# panel.net
KiCad netlist of a schematic drawn in EAGLE
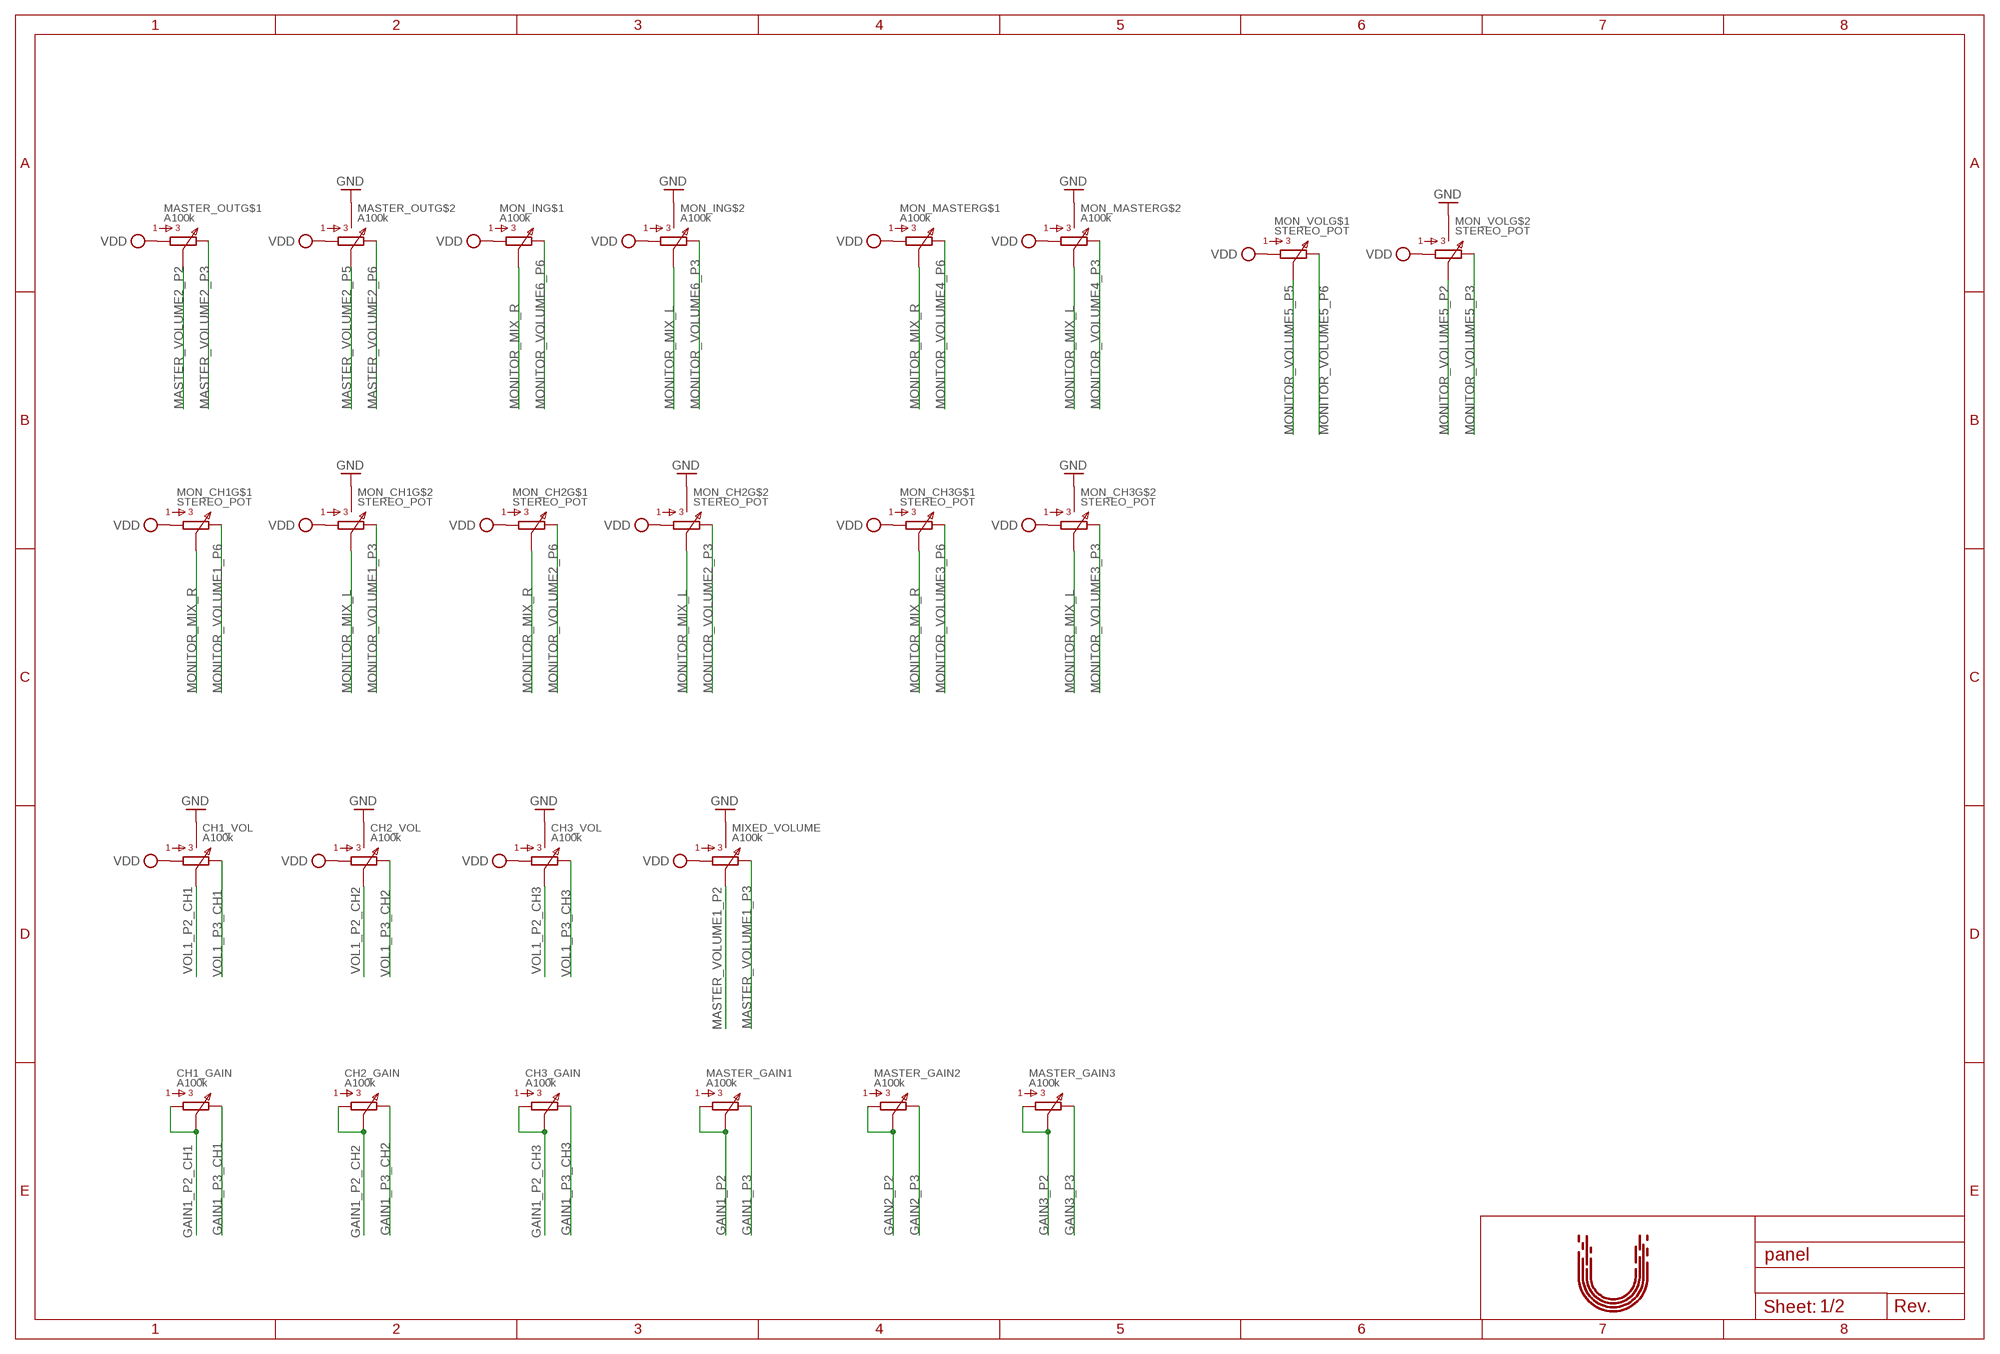
[diagram p0: schematic, sheet 1]
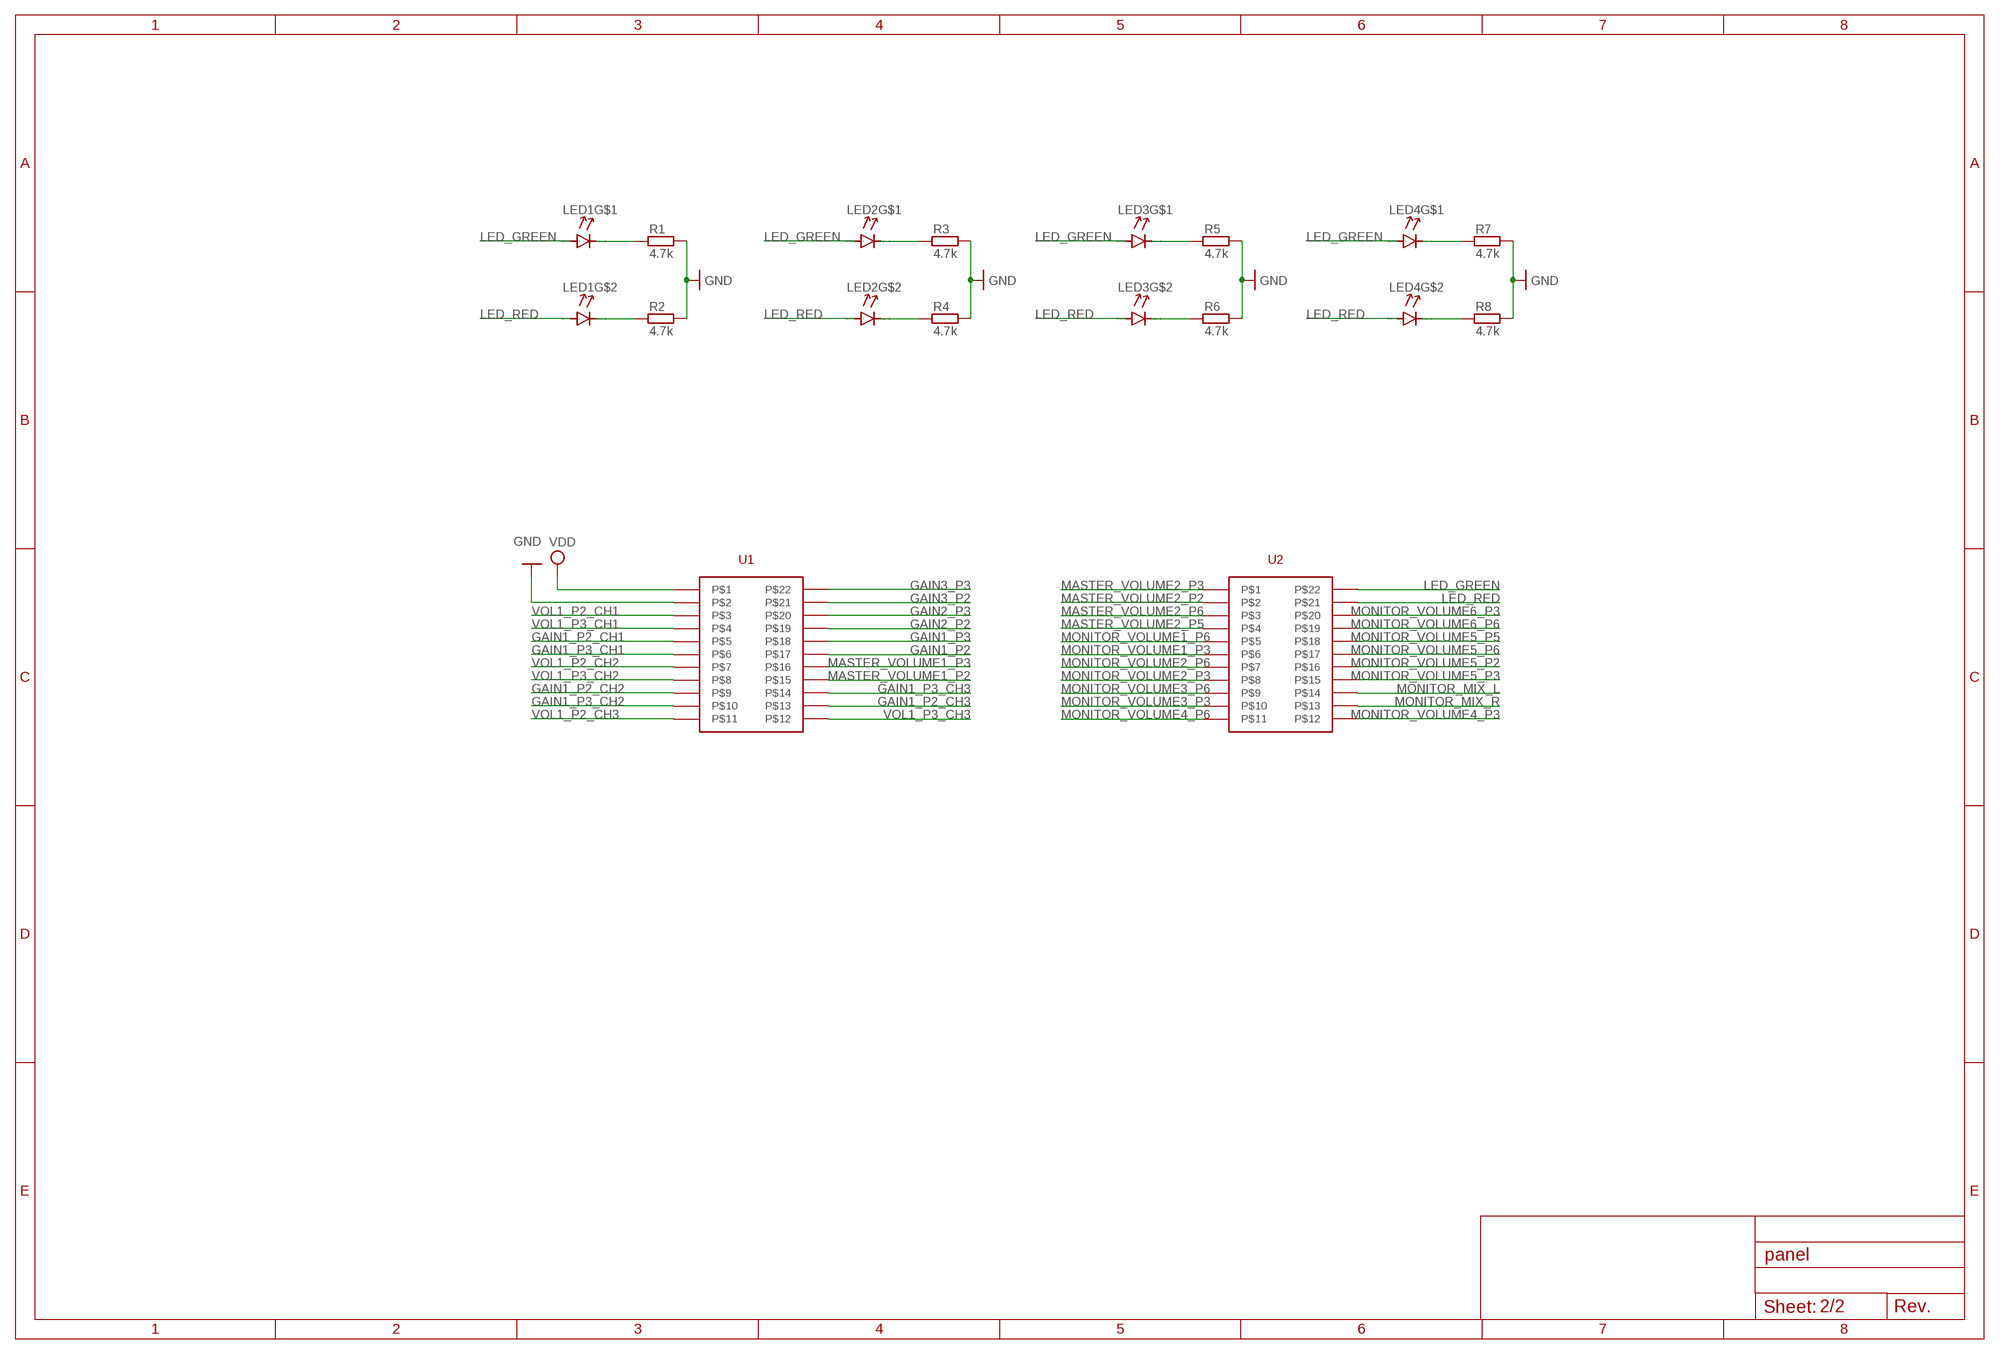
[diagram p1: schematic, sheet 2]

(export (version "E")
  (design (tool "Eeschema 10.0.6"))
  (components
    (comp (ref "CH1_GAIN")
      (value "A100k")
      (footprint "eagle-import:3296W")
      (fields (field (name "MPN") "3296W-1-104RLF"))
      (libsource (lib "eagle-import") (part "TRIMPOT"))
    )
    (comp (ref "CH1_VOL")
      (value "A100k")
      (footprint "eagle-import:P0915N")
      (fields (field (name "MPN") "P0915N-QC15AR100K"))
      (libsource (lib "eagle-import") (part "POT"))
    )
    (comp (ref "CH2_GAIN")
      (value "A100k")
      (footprint "eagle-import:3296W")
      (fields (field (name "MPN") "3296W-1-104RLF"))
      (libsource (lib "eagle-import") (part "TRIMPOT"))
    )
    (comp (ref "CH2_VOL")
      (value "A100k")
      (footprint "eagle-import:P0915N")
      (fields (field (name "MPN") "P0915N-QC15AR100K"))
      (libsource (lib "eagle-import") (part "POT"))
    )
    (comp (ref "CH3_GAIN")
      (value "A100k")
      (footprint "eagle-import:3296W")
      (fields (field (name "MPN") "3296W-1-104RLF"))
      (libsource (lib "eagle-import") (part "TRIMPOT"))
    )
    (comp (ref "CH3_VOL")
      (value "A100k")
      (footprint "eagle-import:P0915N")
      (fields (field (name "MPN") "P0915N-QC15AR100K"))
      (libsource (lib "eagle-import") (part "POT"))
    )
    (comp (ref "MASTER_GAIN1")
      (value "A100k")
      (footprint "eagle-import:3296W")
      (fields (field (name "MPN") "3296W-1-104RLF"))
      (libsource (lib "eagle-import") (part "TRIMPOT"))
    )
    (comp (ref "MASTER_GAIN2")
      (value "A100k")
      (footprint "eagle-import:3296W")
      (fields (field (name "MPN") "3296W-1-104RLF"))
      (libsource (lib "eagle-import") (part "TRIMPOT"))
    )
    (comp (ref "MASTER_GAIN3")
      (value "A100k")
      (footprint "eagle-import:3296W")
      (fields (field (name "MPN") "3296W-1-104RLF"))
      (libsource (lib "eagle-import") (part "TRIMPOT"))
    )
    (comp (ref "MASTER_OUT")
      (value "A100k")
      (footprint "eagle-import:P0925N")
      (fields (field (name "MPN") "P0925N-FC20AR100K"))
      (libsource (lib "eagle-import") (part "STEREO_POT"))
    )
    (comp (ref "MIXED_VOLUME")
      (value "A100k")
      (footprint "eagle-import:P0915N")
      (fields (field (name "MPN") "P0915N-QC15AR100K"))
      (libsource (lib "eagle-import") (part "POT"))
    )
    (comp (ref "MON_CH1")
      (value "STEREO_POT")
      (footprint "eagle-import:P0925N")
      (fields (field (name "MPN") "P0925N-FC20AR100K"))
      (libsource (lib "eagle-import") (part "STEREO_POT"))
    )
    (comp (ref "MON_CH2")
      (value "STEREO_POT")
      (footprint "eagle-import:P0925N")
      (fields (field (name "MPN") "P0925N-FC20AR100K"))
      (libsource (lib "eagle-import") (part "STEREO_POT"))
    )
    (comp (ref "MON_CH3")
      (value "STEREO_POT")
      (footprint "eagle-import:P0925N")
      (fields (field (name "MPN") "P0925N-FC20AR100K"))
      (libsource (lib "eagle-import") (part "STEREO_POT"))
    )
    (comp (ref "MON_IN")
      (value "A100k")
      (footprint "eagle-import:P0925N")
      (fields (field (name "MPN") "P0925N-FC20AR100K"))
      (libsource (lib "eagle-import") (part "STEREO_POT"))
    )
    (comp (ref "MON_MASTER")
      (value "A100k")
      (footprint "eagle-import:P0925N")
      (fields (field (name "MPN") "P0925N-FC20AR100K"))
      (libsource (lib "eagle-import") (part "STEREO_POT"))
    )
    (comp (ref "MON_VOL")
      (value "STEREO_POT")
      (footprint "eagle-import:P0925N")
      (fields (field (name "MPN") "P0925N-FC20AR100K"))
      (libsource (lib "eagle-import") (part "STEREO_POT"))
    )
    (comp (ref "U$1")
      (value "UTBULT_DESIGN4")
      (footprint "eagle-import:UD_4")
      (libsource (lib "eagle-import") (part "UTBULT_DESIGN4"))
    )
    (comp (ref "LED1")
      (value "DUAL_LEDDUAL_LED")
      (footprint "eagle-import:RESCAXE40P80X160X50-4N")
      (fields (field (name "MPN") "HSMF-C162"))
      (libsource (lib "eagle-import") (part "DUAL_LEDDUAL_LED"))
    )
    (comp (ref "LED2")
      (value "DUAL_LEDDUAL_LED")
      (footprint "eagle-import:RESCAXE40P80X160X50-4N")
      (fields (field (name "MPN") "HSMF-C162"))
      (libsource (lib "eagle-import") (part "DUAL_LEDDUAL_LED"))
    )
    (comp (ref "LED3")
      (value "DUAL_LEDDUAL_LED")
      (footprint "eagle-import:RESCAXE40P80X160X50-4N")
      (fields (field (name "MPN") "HSMF-C162"))
      (libsource (lib "eagle-import") (part "DUAL_LEDDUAL_LED"))
    )
    (comp (ref "LED4")
      (value "DUAL_LEDDUAL_LED")
      (footprint "eagle-import:RESCAXE40P80X160X50-4N")
      (fields (field (name "MPN") "HSMF-C162"))
      (libsource (lib "eagle-import") (part "DUAL_LEDDUAL_LED"))
    )
    (comp (ref "R1")
      (value "4.7k")
      (footprint "eagle-import:R0603")
      (libsource (lib "eagle-import") (part "RESISTOR"))
    )
    (comp (ref "R2")
      (value "4.7k")
      (footprint "eagle-import:R0603")
      (libsource (lib "eagle-import") (part "RESISTOR"))
    )
    (comp (ref "R3")
      (value "4.7k")
      (footprint "eagle-import:R0603")
      (libsource (lib "eagle-import") (part "RESISTOR"))
    )
    (comp (ref "R4")
      (value "4.7k")
      (footprint "eagle-import:R0603")
      (libsource (lib "eagle-import") (part "RESISTOR"))
    )
    (comp (ref "R5")
      (value "4.7k")
      (footprint "eagle-import:R0603")
      (libsource (lib "eagle-import") (part "RESISTOR"))
    )
    (comp (ref "R6")
      (value "4.7k")
      (footprint "eagle-import:R0603")
      (libsource (lib "eagle-import") (part "RESISTOR"))
    )
    (comp (ref "R7")
      (value "4.7k")
      (footprint "eagle-import:R0603")
      (libsource (lib "eagle-import") (part "RESISTOR"))
    )
    (comp (ref "R8")
      (value "4.7k")
      (footprint "eagle-import:R0603")
      (libsource (lib "eagle-import") (part "RESISTOR"))
    )
    (comp (ref "U1")
      (value "22PINHEADER22PINHEADER")
      (footprint "eagle-import:HDRV22W64P254_2X11_2794X508X838B")
      (libsource (lib "eagle-import") (part "22PINHEADER22PINHEADER"))
    )
    (comp (ref "U2")
      (value "22PINHEADER22PINHEADER")
      (footprint "eagle-import:HDRV22W64P254_2X11_2794X508X838B")
      (libsource (lib "eagle-import") (part "22PINHEADER22PINHEADER"))
    )
  )
  (nets
    (net (code "1") (name "GAIN1_P2") (class "Default")
      (node (ref "MASTER_GAIN1") (pin "P$1") (pinfunction "1_P$1") (pintype "passive"))
      (node (ref "MASTER_GAIN1") (pin "P$2") (pinfunction "2_P$2") (pintype "passive"))
      (node (ref "U1") (pin "17") (pinfunction "P$17_17") (pintype "bidirectional"))
    )
    (net (code "2") (name "GAIN1_P2_CH1") (class "Default")
      (node (ref "CH1_GAIN") (pin "P$1") (pinfunction "1_P$1") (pintype "passive"))
      (node (ref "CH1_GAIN") (pin "P$2") (pinfunction "2_P$2") (pintype "passive"))
      (node (ref "U1") (pin "5") (pinfunction "P$5_5") (pintype "bidirectional"))
    )
    (net (code "3") (name "GAIN1_P2_CH2") (class "Default")
      (node (ref "CH2_GAIN") (pin "P$1") (pinfunction "1_P$1") (pintype "passive"))
      (node (ref "CH2_GAIN") (pin "P$2") (pinfunction "2_P$2") (pintype "passive"))
      (node (ref "U1") (pin "9") (pinfunction "P$9_9") (pintype "bidirectional"))
    )
    (net (code "4") (name "GAIN1_P2_CH3") (class "Default")
      (node (ref "CH3_GAIN") (pin "P$1") (pinfunction "1_P$1") (pintype "passive"))
      (node (ref "CH3_GAIN") (pin "P$2") (pinfunction "2_P$2") (pintype "passive"))
      (node (ref "U1") (pin "13") (pinfunction "P$13_13") (pintype "bidirectional"))
    )
    (net (code "5") (name "GAIN1_P3") (class "Default")
      (node (ref "MASTER_GAIN1") (pin "P$3") (pinfunction "3_P$3") (pintype "passive"))
      (node (ref "U1") (pin "18") (pinfunction "P$18_18") (pintype "bidirectional"))
    )
    (net (code "6") (name "GAIN1_P3_CH1") (class "Default")
      (node (ref "CH1_GAIN") (pin "P$3") (pinfunction "3_P$3") (pintype "passive"))
      (node (ref "U1") (pin "6") (pinfunction "P$6_6") (pintype "bidirectional"))
    )
    (net (code "7") (name "GAIN1_P3_CH2") (class "Default")
      (node (ref "CH2_GAIN") (pin "P$3") (pinfunction "3_P$3") (pintype "passive"))
      (node (ref "U1") (pin "10") (pinfunction "P$10_10") (pintype "bidirectional"))
    )
    (net (code "8") (name "GAIN1_P3_CH3") (class "Default")
      (node (ref "CH3_GAIN") (pin "P$3") (pinfunction "3_P$3") (pintype "passive"))
      (node (ref "U1") (pin "14") (pinfunction "P$14_14") (pintype "bidirectional"))
    )
    (net (code "9") (name "GAIN2_P2") (class "Default")
      (node (ref "MASTER_GAIN2") (pin "P$1") (pinfunction "1_P$1") (pintype "passive"))
      (node (ref "MASTER_GAIN2") (pin "P$2") (pinfunction "2_P$2") (pintype "passive"))
      (node (ref "U1") (pin "19") (pinfunction "P$19_19") (pintype "bidirectional"))
    )
    (net (code "10") (name "GAIN2_P3") (class "Default")
      (node (ref "MASTER_GAIN2") (pin "P$3") (pinfunction "3_P$3") (pintype "passive"))
      (node (ref "U1") (pin "20") (pinfunction "P$20_20") (pintype "bidirectional"))
    )
    (net (code "11") (name "GAIN3_P2") (class "Default")
      (node (ref "MASTER_GAIN3") (pin "P$1") (pinfunction "1_P$1") (pintype "passive"))
      (node (ref "MASTER_GAIN3") (pin "P$2") (pinfunction "2_P$2") (pintype "passive"))
      (node (ref "U1") (pin "21") (pinfunction "P$21_21") (pintype "bidirectional"))
    )
    (net (code "12") (name "GAIN3_P3") (class "Default")
      (node (ref "MASTER_GAIN3") (pin "P$3") (pinfunction "3_P$3") (pintype "passive"))
      (node (ref "U1") (pin "22") (pinfunction "P$22_22") (pintype "bidirectional"))
    )
    (net (code "13") (name "GND") (class "Default")
      (node (ref "CH1_VOL") (pin "P$7") (pinfunction "P$1_P$7") (pintype "bidirectional"))
      (node (ref "CH1_VOL") (pin "P$8") (pinfunction "P$1_P$8") (pintype "bidirectional"))
      (node (ref "CH2_VOL") (pin "P$7") (pinfunction "P$1_P$7") (pintype "bidirectional"))
      (node (ref "CH2_VOL") (pin "P$8") (pinfunction "P$1_P$8") (pintype "bidirectional"))
      (node (ref "CH3_VOL") (pin "P$7") (pinfunction "P$1_P$7") (pintype "bidirectional"))
      (node (ref "CH3_VOL") (pin "P$8") (pinfunction "P$1_P$8") (pintype "bidirectional"))
      (node (ref "MASTER_OUT") (pin "P$7") (pinfunction "P$1_P$7") (pintype "bidirectional"))
      (node (ref "MASTER_OUT") (pin "P$8") (pinfunction "P$1_P$8") (pintype "bidirectional"))
      (node (ref "MIXED_VOLUME") (pin "P$7") (pinfunction "P$1_P$7") (pintype "bidirectional"))
      (node (ref "MIXED_VOLUME") (pin "P$8") (pinfunction "P$1_P$8") (pintype "bidirectional"))
      (node (ref "MON_CH1") (pin "P$7") (pinfunction "P$1_P$7") (pintype "bidirectional"))
      (node (ref "MON_CH1") (pin "P$8") (pinfunction "P$1_P$8") (pintype "bidirectional"))
      (node (ref "MON_CH2") (pin "P$7") (pinfunction "P$1_P$7") (pintype "bidirectional"))
      (node (ref "MON_CH2") (pin "P$8") (pinfunction "P$1_P$8") (pintype "bidirectional"))
      (node (ref "MON_CH3") (pin "P$7") (pinfunction "P$1_P$7") (pintype "bidirectional"))
      (node (ref "MON_CH3") (pin "P$8") (pinfunction "P$1_P$8") (pintype "bidirectional"))
      (node (ref "MON_IN") (pin "P$7") (pinfunction "P$1_P$7") (pintype "bidirectional"))
      (node (ref "MON_IN") (pin "P$8") (pinfunction "P$1_P$8") (pintype "bidirectional"))
      (node (ref "MON_MASTER") (pin "P$7") (pinfunction "P$1_P$7") (pintype "bidirectional"))
      (node (ref "MON_MASTER") (pin "P$8") (pinfunction "P$1_P$8") (pintype "bidirectional"))
      (node (ref "MON_VOL") (pin "P$7") (pinfunction "P$1_P$7") (pintype "bidirectional"))
      (node (ref "MON_VOL") (pin "P$8") (pinfunction "P$1_P$8") (pintype "bidirectional"))
      (node (ref "R1") (pin "2") (pinfunction "2_2") (pintype "passive"))
      (node (ref "R2") (pin "2") (pinfunction "2_2") (pintype "passive"))
      (node (ref "R3") (pin "2") (pinfunction "2_2") (pintype "passive"))
      (node (ref "R4") (pin "2") (pinfunction "2_2") (pintype "passive"))
      (node (ref "R5") (pin "2") (pinfunction "2_2") (pintype "passive"))
      (node (ref "R6") (pin "2") (pinfunction "2_2") (pintype "passive"))
      (node (ref "R7") (pin "2") (pinfunction "2_2") (pintype "passive"))
      (node (ref "R8") (pin "2") (pinfunction "2_2") (pintype "passive"))
      (node (ref "U1") (pin "2") (pinfunction "P$2_2") (pintype "bidirectional"))
    )
    (net (code "14") (name "LED_GREEN") (class "Default")
      (node (ref "LED1") (pin "1") (pinfunction "A_1") (pintype "passive"))
      (node (ref "LED2") (pin "1") (pinfunction "A_1") (pintype "passive"))
      (node (ref "LED3") (pin "1") (pinfunction "A_1") (pintype "passive"))
      (node (ref "LED4") (pin "1") (pinfunction "A_1") (pintype "passive"))
      (node (ref "U2") (pin "22") (pinfunction "P$22_22") (pintype "bidirectional"))
    )
    (net (code "15") (name "LED_RED") (class "Default")
      (node (ref "LED1") (pin "2") (pinfunction "A_2") (pintype "passive"))
      (node (ref "LED2") (pin "2") (pinfunction "A_2") (pintype "passive"))
      (node (ref "LED3") (pin "2") (pinfunction "A_2") (pintype "passive"))
      (node (ref "LED4") (pin "2") (pinfunction "A_2") (pintype "passive"))
      (node (ref "U2") (pin "21") (pinfunction "P$21_21") (pintype "bidirectional"))
    )
    (net (code "16") (name "MASTER_VOLUME1_P2") (class "Default")
      (node (ref "MIXED_VOLUME") (pin "P$2") (pinfunction "2_P$2") (pintype "passive"))
      (node (ref "U1") (pin "15") (pinfunction "P$15_15") (pintype "bidirectional"))
    )
    (net (code "17") (name "MASTER_VOLUME1_P3") (class "Default")
      (node (ref "MIXED_VOLUME") (pin "P$3") (pinfunction "3_P$3") (pintype "passive"))
      (node (ref "U1") (pin "16") (pinfunction "P$16_16") (pintype "bidirectional"))
    )
    (net (code "18") (name "MASTER_VOLUME2_P2") (class "Default")
      (node (ref "MASTER_OUT") (pin "P$2") (pinfunction "2_P$2") (pintype "passive"))
      (node (ref "U2") (pin "2") (pinfunction "P$2_2") (pintype "bidirectional"))
    )
    (net (code "19") (name "MASTER_VOLUME2_P3") (class "Default")
      (node (ref "MASTER_OUT") (pin "P$3") (pinfunction "3_P$3") (pintype "passive"))
      (node (ref "U2") (pin "1") (pinfunction "P$1_1") (pintype "bidirectional"))
    )
    (net (code "20") (name "MASTER_VOLUME2_P5") (class "Default")
      (node (ref "MASTER_OUT") (pin "P$5") (pinfunction "2_P$5") (pintype "passive"))
      (node (ref "U2") (pin "4") (pinfunction "P$4_4") (pintype "bidirectional"))
    )
    (net (code "21") (name "MASTER_VOLUME2_P6") (class "Default")
      (node (ref "MASTER_OUT") (pin "P$6") (pinfunction "3_P$6") (pintype "passive"))
      (node (ref "U2") (pin "3") (pinfunction "P$3_3") (pintype "bidirectional"))
    )
    (net (code "22") (name "MONITOR_MIX_L") (class "Default")
      (node (ref "MON_CH1") (pin "P$5") (pinfunction "2_P$5") (pintype "passive"))
      (node (ref "MON_CH2") (pin "P$5") (pinfunction "2_P$5") (pintype "passive"))
      (node (ref "MON_CH3") (pin "P$5") (pinfunction "2_P$5") (pintype "passive"))
      (node (ref "MON_IN") (pin "P$5") (pinfunction "2_P$5") (pintype "passive"))
      (node (ref "MON_MASTER") (pin "P$5") (pinfunction "2_P$5") (pintype "passive"))
      (node (ref "U2") (pin "14") (pinfunction "P$14_14") (pintype "bidirectional"))
    )
    (net (code "23") (name "MONITOR_MIX_R") (class "Default")
      (node (ref "MON_CH1") (pin "P$2") (pinfunction "2_P$2") (pintype "passive"))
      (node (ref "MON_CH2") (pin "P$2") (pinfunction "2_P$2") (pintype "passive"))
      (node (ref "MON_CH3") (pin "P$2") (pinfunction "2_P$2") (pintype "passive"))
      (node (ref "MON_IN") (pin "P$2") (pinfunction "2_P$2") (pintype "passive"))
      (node (ref "MON_MASTER") (pin "P$2") (pinfunction "2_P$2") (pintype "passive"))
      (node (ref "U2") (pin "13") (pinfunction "P$13_13") (pintype "bidirectional"))
    )
    (net (code "24") (name "MONITOR_VOLUME1_P3") (class "Default")
      (node (ref "MON_CH1") (pin "P$6") (pinfunction "3_P$6") (pintype "passive"))
      (node (ref "U2") (pin "6") (pinfunction "P$6_6") (pintype "bidirectional"))
    )
    (net (code "25") (name "MONITOR_VOLUME1_P6") (class "Default")
      (node (ref "MON_CH1") (pin "P$3") (pinfunction "3_P$3") (pintype "passive"))
      (node (ref "U2") (pin "5") (pinfunction "P$5_5") (pintype "bidirectional"))
    )
    (net (code "26") (name "MONITOR_VOLUME2_P3") (class "Default")
      (node (ref "MON_CH2") (pin "P$6") (pinfunction "3_P$6") (pintype "passive"))
      (node (ref "U2") (pin "8") (pinfunction "P$8_8") (pintype "bidirectional"))
    )
    (net (code "27") (name "MONITOR_VOLUME2_P6") (class "Default")
      (node (ref "MON_CH2") (pin "P$3") (pinfunction "3_P$3") (pintype "passive"))
      (node (ref "U2") (pin "7") (pinfunction "P$7_7") (pintype "bidirectional"))
    )
    (net (code "28") (name "MONITOR_VOLUME3_P3") (class "Default")
      (node (ref "MON_CH3") (pin "P$6") (pinfunction "3_P$6") (pintype "passive"))
      (node (ref "U2") (pin "10") (pinfunction "P$10_10") (pintype "bidirectional"))
    )
    (net (code "29") (name "MONITOR_VOLUME3_P6") (class "Default")
      (node (ref "MON_CH3") (pin "P$3") (pinfunction "3_P$3") (pintype "passive"))
      (node (ref "U2") (pin "9") (pinfunction "P$9_9") (pintype "bidirectional"))
    )
    (net (code "30") (name "MONITOR_VOLUME4_P3") (class "Default")
      (node (ref "MON_MASTER") (pin "P$6") (pinfunction "3_P$6") (pintype "passive"))
      (node (ref "U2") (pin "12") (pinfunction "P$12_12") (pintype "bidirectional"))
    )
    (net (code "31") (name "MONITOR_VOLUME4_P6") (class "Default")
      (node (ref "MON_MASTER") (pin "P$3") (pinfunction "3_P$3") (pintype "passive"))
      (node (ref "U2") (pin "11") (pinfunction "P$11_11") (pintype "bidirectional"))
    )
    (net (code "32") (name "MONITOR_VOLUME5_P2") (class "Default")
      (node (ref "MON_VOL") (pin "P$5") (pinfunction "2_P$5") (pintype "passive"))
      (node (ref "U2") (pin "16") (pinfunction "P$16_16") (pintype "bidirectional"))
    )
    (net (code "33") (name "MONITOR_VOLUME5_P3") (class "Default")
      (node (ref "MON_VOL") (pin "P$6") (pinfunction "3_P$6") (pintype "passive"))
      (node (ref "U2") (pin "15") (pinfunction "P$15_15") (pintype "bidirectional"))
    )
    (net (code "34") (name "MONITOR_VOLUME5_P5") (class "Default")
      (node (ref "MON_VOL") (pin "P$2") (pinfunction "2_P$2") (pintype "passive"))
      (node (ref "U2") (pin "18") (pinfunction "P$18_18") (pintype "bidirectional"))
    )
    (net (code "35") (name "MONITOR_VOLUME5_P6") (class "Default")
      (node (ref "MON_VOL") (pin "P$3") (pinfunction "3_P$3") (pintype "passive"))
      (node (ref "U2") (pin "17") (pinfunction "P$17_17") (pintype "bidirectional"))
    )
    (net (code "36") (name "MONITOR_VOLUME6_P3") (class "Default")
      (node (ref "MON_IN") (pin "P$6") (pinfunction "3_P$6") (pintype "passive"))
      (node (ref "U2") (pin "20") (pinfunction "P$20_20") (pintype "bidirectional"))
    )
    (net (code "37") (name "MONITOR_VOLUME6_P6") (class "Default")
      (node (ref "MON_IN") (pin "P$3") (pinfunction "3_P$3") (pintype "passive"))
      (node (ref "U2") (pin "19") (pinfunction "P$19_19") (pintype "bidirectional"))
    )
    (net (code "38") (name "Net-(LED1A-C)") (class "Default")
      (node (ref "LED1") (pin "4") (pinfunction "C_4") (pintype "passive"))
      (node (ref "R1") (pin "1") (pinfunction "1_1") (pintype "passive"))
    )
    (net (code "39") (name "Net-(LED1B-C)") (class "Default")
      (node (ref "LED1") (pin "3") (pinfunction "C_3") (pintype "passive"))
      (node (ref "R2") (pin "1") (pinfunction "1_1") (pintype "passive"))
    )
    (net (code "40") (name "Net-(LED2A-C)") (class "Default")
      (node (ref "LED2") (pin "4") (pinfunction "C_4") (pintype "passive"))
      (node (ref "R3") (pin "1") (pinfunction "1_1") (pintype "passive"))
    )
    (net (code "41") (name "Net-(LED2B-C)") (class "Default")
      (node (ref "LED2") (pin "3") (pinfunction "C_3") (pintype "passive"))
      (node (ref "R4") (pin "1") (pinfunction "1_1") (pintype "passive"))
    )
    (net (code "42") (name "Net-(LED3A-C)") (class "Default")
      (node (ref "LED3") (pin "4") (pinfunction "C_4") (pintype "passive"))
      (node (ref "R5") (pin "1") (pinfunction "1_1") (pintype "passive"))
    )
    (net (code "43") (name "Net-(LED3B-C)") (class "Default")
      (node (ref "LED3") (pin "3") (pinfunction "C_3") (pintype "passive"))
      (node (ref "R6") (pin "1") (pinfunction "1_1") (pintype "passive"))
    )
    (net (code "44") (name "Net-(LED4A-C)") (class "Default")
      (node (ref "LED4") (pin "4") (pinfunction "C_4") (pintype "passive"))
      (node (ref "R7") (pin "1") (pinfunction "1_1") (pintype "passive"))
    )
    (net (code "45") (name "Net-(LED4B-C)") (class "Default")
      (node (ref "LED4") (pin "3") (pinfunction "C_3") (pintype "passive"))
      (node (ref "R8") (pin "1") (pinfunction "1_1") (pintype "passive"))
    )
    (net (code "46") (name "VDD") (class "Default")
      (node (ref "CH1_VOL") (pin "P$1") (pinfunction "1_P$1") (pintype "passive"))
      (node (ref "CH2_VOL") (pin "P$1") (pinfunction "1_P$1") (pintype "passive"))
      (node (ref "CH3_VOL") (pin "P$1") (pinfunction "1_P$1") (pintype "passive"))
      (node (ref "MASTER_OUT") (pin "P$1") (pinfunction "1_P$1") (pintype "passive"))
      (node (ref "MASTER_OUT") (pin "P$4") (pinfunction "1_P$4") (pintype "passive"))
      (node (ref "MIXED_VOLUME") (pin "P$1") (pinfunction "1_P$1") (pintype "passive"))
      (node (ref "MON_CH1") (pin "P$1") (pinfunction "1_P$1") (pintype "passive"))
      (node (ref "MON_CH1") (pin "P$4") (pinfunction "1_P$4") (pintype "passive"))
      (node (ref "MON_CH2") (pin "P$1") (pinfunction "1_P$1") (pintype "passive"))
      (node (ref "MON_CH2") (pin "P$4") (pinfunction "1_P$4") (pintype "passive"))
      (node (ref "MON_CH3") (pin "P$1") (pinfunction "1_P$1") (pintype "passive"))
      (node (ref "MON_CH3") (pin "P$4") (pinfunction "1_P$4") (pintype "passive"))
      (node (ref "MON_IN") (pin "P$1") (pinfunction "1_P$1") (pintype "passive"))
      (node (ref "MON_IN") (pin "P$4") (pinfunction "1_P$4") (pintype "passive"))
      (node (ref "MON_MASTER") (pin "P$1") (pinfunction "1_P$1") (pintype "passive"))
      (node (ref "MON_MASTER") (pin "P$4") (pinfunction "1_P$4") (pintype "passive"))
      (node (ref "MON_VOL") (pin "P$1") (pinfunction "1_P$1") (pintype "passive"))
      (node (ref "MON_VOL") (pin "P$4") (pinfunction "1_P$4") (pintype "passive"))
      (node (ref "U1") (pin "1") (pinfunction "P$1_1") (pintype "bidirectional"))
    )
    (net (code "47") (name "VOL1_P2_CH1") (class "Default")
      (node (ref "CH1_VOL") (pin "P$2") (pinfunction "2_P$2") (pintype "passive"))
      (node (ref "U1") (pin "3") (pinfunction "P$3_3") (pintype "bidirectional"))
    )
    (net (code "48") (name "VOL1_P2_CH2") (class "Default")
      (node (ref "CH2_VOL") (pin "P$2") (pinfunction "2_P$2") (pintype "passive"))
      (node (ref "U1") (pin "7") (pinfunction "P$7_7") (pintype "bidirectional"))
    )
    (net (code "49") (name "VOL1_P2_CH3") (class "Default")
      (node (ref "CH3_VOL") (pin "P$2") (pinfunction "2_P$2") (pintype "passive"))
      (node (ref "U1") (pin "11") (pinfunction "P$11_11") (pintype "bidirectional"))
    )
    (net (code "50") (name "VOL1_P3_CH1") (class "Default")
      (node (ref "CH1_VOL") (pin "P$3") (pinfunction "3_P$3") (pintype "passive"))
      (node (ref "U1") (pin "4") (pinfunction "P$4_4") (pintype "bidirectional"))
    )
    (net (code "51") (name "VOL1_P3_CH2") (class "Default")
      (node (ref "CH2_VOL") (pin "P$3") (pinfunction "3_P$3") (pintype "passive"))
      (node (ref "U1") (pin "8") (pinfunction "P$8_8") (pintype "bidirectional"))
    )
    (net (code "52") (name "VOL1_P3_CH3") (class "Default")
      (node (ref "CH3_VOL") (pin "P$3") (pinfunction "3_P$3") (pintype "passive"))
      (node (ref "U1") (pin "12") (pinfunction "P$12_12") (pintype "bidirectional"))
    )
  )
)
